# ATM90E26_Featherwing.net
KiCad netlist of a schematic drawn in EAGLE
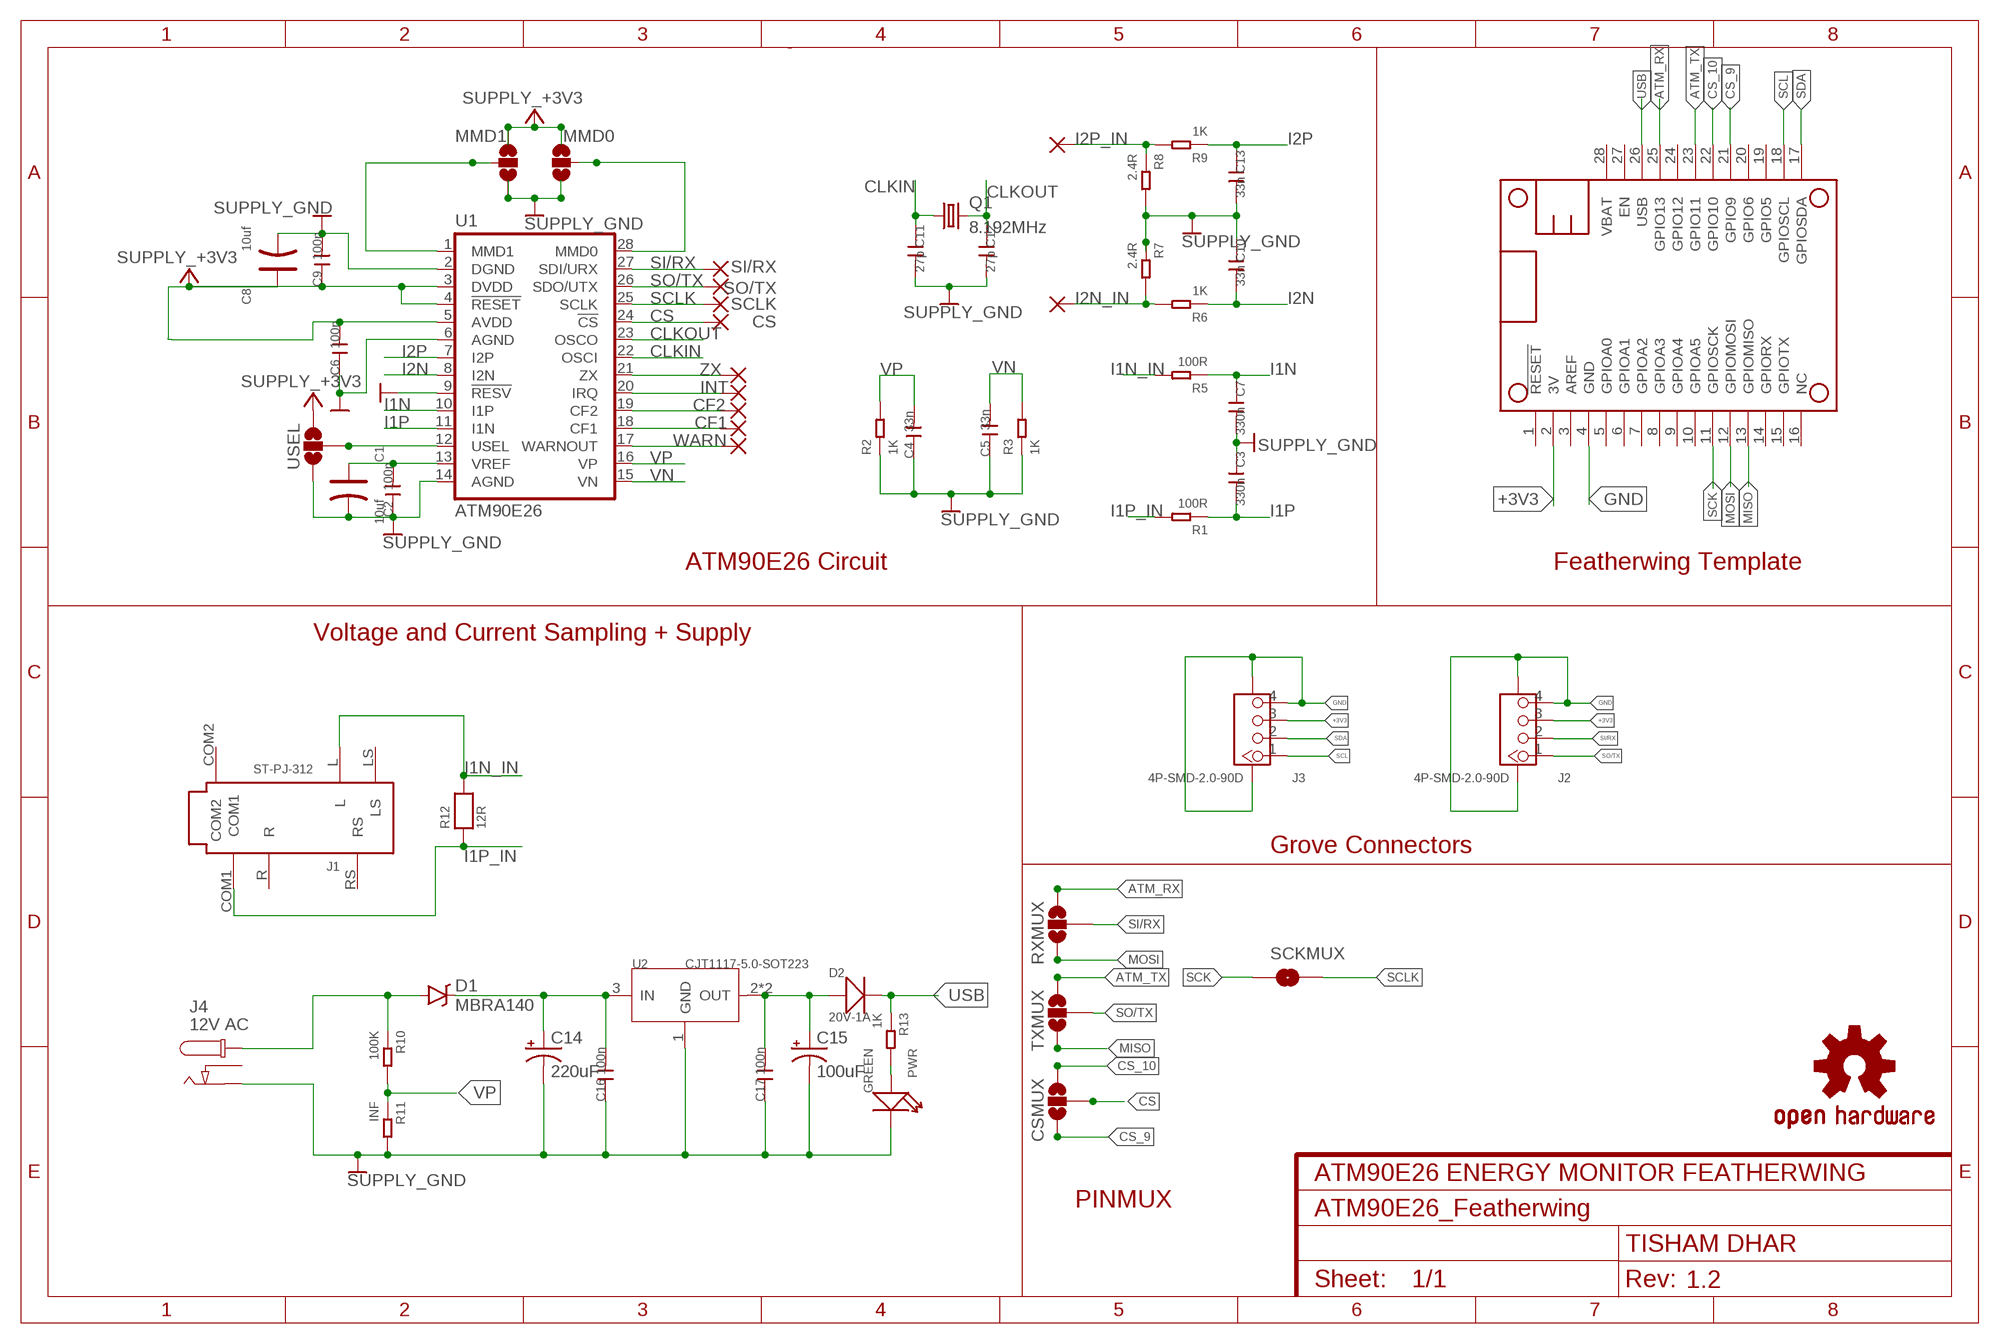
[diagram p0: schematic, sheet 1]

(export (version "E")
  (design (tool "Eeschema 10.0.6"))
  (components
    (comp (ref "C1")
      (value "10uf")
      (footprint "eagle-import:AVX-A")
      (fields (field (name "MPN") "TAJA226*010#NJ"))
      (libsource (lib "eagle-import") (part "TANTALUM-SMD-22UF-10V(AVX-A)"))
    )
    (comp (ref "C2")
      (value "100n")
      (footprint "eagle-import:C0603")
      (libsource (lib "eagle-import") (part "C-0603"))
    )
    (comp (ref "C3")
      (value "330n")
      (footprint "eagle-import:C0603")
      (libsource (lib "eagle-import") (part "C-0603"))
    )
    (comp (ref "C4")
      (value "33n")
      (footprint "eagle-import:C0603")
      (libsource (lib "eagle-import") (part "C-0603"))
    )
    (comp (ref "C5")
      (value "33n")
      (footprint "eagle-import:C0603")
      (libsource (lib "eagle-import") (part "C-0603"))
    )
    (comp (ref "C6")
      (value "100n")
      (footprint "eagle-import:C0603")
      (libsource (lib "eagle-import") (part "C-0603"))
    )
    (comp (ref "C7")
      (value "330n")
      (footprint "eagle-import:C0603")
      (libsource (lib "eagle-import") (part "C-0603"))
    )
    (comp (ref "C8")
      (value "10uf")
      (footprint "eagle-import:AVX-A")
      (fields (field (name "MPN") "TAJA226*010#NJ"))
      (libsource (lib "eagle-import") (part "TANTALUM-SMD-22UF-10V(AVX-A)"))
    )
    (comp (ref "C9")
      (value "100n")
      (footprint "eagle-import:C0603")
      (libsource (lib "eagle-import") (part "C-0603"))
    )
    (comp (ref "C10")
      (value "33n")
      (footprint "eagle-import:C0603")
      (libsource (lib "eagle-import") (part "C-0603"))
    )
    (comp (ref "C11")
      (value "27p")
      (footprint "eagle-import:C0603")
      (libsource (lib "eagle-import") (part "C-0603"))
    )
    (comp (ref "C12")
      (value "27p")
      (footprint "eagle-import:C0603")
      (libsource (lib "eagle-import") (part "C-0603"))
    )
    (comp (ref "C13")
      (value "33n")
      (footprint "eagle-import:C0603")
      (libsource (lib "eagle-import") (part "C-0603"))
    )
    (comp (ref "C14")
      (value "220uF")
      (footprint "eagle-import:140CLH-1010")
      (libsource (lib "eagle-import") (part "CPOL-US140CLH-1010"))
    )
    (comp (ref "C15")
      (value "100uF")
      (footprint "eagle-import:153CLV-0605")
      (libsource (lib "eagle-import") (part "CPOL-US153CLV-0605"))
    )
    (comp (ref "C16")
      (value "100n")
      (footprint "eagle-import:C0603")
      (libsource (lib "eagle-import") (part "C-0603"))
    )
    (comp (ref "C17")
      (value "100n")
      (footprint "eagle-import:C0603")
      (libsource (lib "eagle-import") (part "C-0603"))
    )
    (comp (ref "CF1")
      (value "WIREPADSMD1,27-254")
      (footprint "eagle-import:SMD1,27-2,54")
      (libsource (lib "eagle-import") (part "WIREPADSMD1,27-254"))
    )
    (comp (ref "CF2")
      (value "WIREPADSMD1,27-254")
      (footprint "eagle-import:SMD1,27-2,54")
      (libsource (lib "eagle-import") (part "WIREPADSMD1,27-254"))
    )
    (comp (ref "CS")
      (value "WIREPADSMD1,27-254")
      (footprint "eagle-import:SMD1,27-2,54")
      (libsource (lib "eagle-import") (part "WIREPADSMD1,27-254"))
    )
    (comp (ref "CSMUX")
      (value "JUMPER-PAD-3-NOYES_SILK")
      (footprint "eagle-import:PAD-JUMPER-3-NO_YES_SILK")
      (libsource (lib "eagle-import") (part "JUMPER-PAD-3-NOYES_SILK"))
    )
    (comp (ref "D1")
      (value "MBRA140")
      (footprint "eagle-import:SMA-DIODE")
      (libsource (lib "eagle-import") (part "MBRA140"))
    )
    (comp (ref "D2")
      (value "20V-1A")
      (footprint "eagle-import:SOD-123")
      (fields (field (name "MPN") "B5819W"))
      (libsource (lib "eagle-import") (part "SMD-DIODE-SCHOTTKY-20V-1A(SOD-123)"))
    )
    (comp (ref "I2N_IN")
      (value "WIREPADSMD1,27-254")
      (footprint "eagle-import:SMD1,27-2,54")
      (libsource (lib "eagle-import") (part "WIREPADSMD1,27-254"))
    )
    (comp (ref "I2P_IN")
      (value "WIREPADSMD1,27-254")
      (footprint "eagle-import:SMD1,27-2,54")
      (libsource (lib "eagle-import") (part "WIREPADSMD1,27-254"))
    )
    (comp (ref "INT")
      (value "WIREPADSMD1,27-254")
      (footprint "eagle-import:SMD1,27-2,54")
      (libsource (lib "eagle-import") (part "WIREPADSMD1,27-254"))
    )
    (comp (ref "J1")
      (value "ST-PJ-312")
      (footprint "eagle-import:AUDIO6P-SMD-3.5-14.0X6.4X5.0MM")
      (libsource (lib "eagle-import") (part "AUDIO-JACK-6P-SMD(ST-PJ-312)"))
    )
    (comp (ref "J2")
      (value "4P-SMD-2.0-90D")
      (footprint "eagle-import:HW4-SMD-2.0-90D")
      (libsource (lib "eagle-import") (part "GROVE-CONNECTOR-SMD-90D(4+2P-2.0)"))
    )
    (comp (ref "J3")
      (value "4P-SMD-2.0-90D")
      (footprint "eagle-import:HW4-SMD-2.0-90D")
      (libsource (lib "eagle-import") (part "GROVE-CONNECTOR-SMD-90D(4+2P-2.0)"))
    )
    (comp (ref "J4")
      (value "12V AC")
      (footprint "eagle-import:DC_BARREL_JACK_SMD_2MM")
      (libsource (lib "eagle-import") (part "CON_DC_M-DC_SMD"))
    )
    (comp (ref "LOGO1")
      (value "OSHW-LOGOM")
      (footprint "eagle-import:OSHW-LOGO-M")
      (libsource (lib "eagle-import") (part "OSHW-LOGOM"))
    )
    (comp (ref "MMD0")
      (value "JUMPER-PAD-3-NOFULL_BOX_SILK")
      (footprint "eagle-import:PAD-JUMPER-3-NO_YES_SILK_FULL_BOX")
      (libsource (lib "eagle-import") (part "JUMPER-PAD-3-NOFULL_BOX_SILK"))
    )
    (comp (ref "MMD1")
      (value "JUMPER-PAD-3-NOFULL_BOX_SILK")
      (footprint "eagle-import:PAD-JUMPER-3-NO_YES_SILK_FULL_BOX")
      (libsource (lib "eagle-import") (part "JUMPER-PAD-3-NOFULL_BOX_SILK"))
    )
    (comp (ref "MS1")
      (value "FEATHERWING_NODIM")
      (footprint "eagle-import:FEATHERWING_DIM")
      (libsource (lib "eagle-import") (part "FEATHERWING_NODIM"))
    )
    (comp (ref "PWR")
      (value "GREEN")
      (footprint "eagle-import:LED-0603")
      (libsource (lib "eagle-import") (part "LED'0603'"))
    )
    (comp (ref "Q1")
      (value "8.192MHz")
      (footprint "eagle-import:HC49UP")
      (libsource (lib "eagle-import") (part "CRYSTALHC49UP"))
    )
    (comp (ref "R1")
      (value "100R")
      (footprint "eagle-import:R0603")
      (fields (field (name "MPN") "RC0603FR-071KL"))
      (libsource (lib "eagle-import") (part "SMD-RES-1K(0603)"))
    )
    (comp (ref "R2")
      (value "1K")
      (footprint "eagle-import:R0603")
      (fields (field (name "MPN") "RC0603FR-071KL"))
      (libsource (lib "eagle-import") (part "SMD-RES-1K(0603)"))
    )
    (comp (ref "R3")
      (value "1K")
      (footprint "eagle-import:R0603")
      (fields (field (name "MPN") "RC0603FR-071KL"))
      (libsource (lib "eagle-import") (part "SMD-RES-1K(0603)"))
    )
    (comp (ref "R5")
      (value "100R")
      (footprint "eagle-import:R0603")
      (fields (field (name "MPN") "RC0603FR-071KL"))
      (libsource (lib "eagle-import") (part "SMD-RES-1K(0603)"))
    )
    (comp (ref "R6")
      (value "1K")
      (footprint "eagle-import:R0603")
      (fields (field (name "MPN") "RC0603FR-071KL"))
      (libsource (lib "eagle-import") (part "SMD-RES-1K(0603)"))
    )
    (comp (ref "R7")
      (value "2.4R")
      (footprint "eagle-import:R0603")
      (fields (field (name "MPN") "RC0603FR-071KL"))
      (libsource (lib "eagle-import") (part "SMD-RES-1K(0603)"))
    )
    (comp (ref "R8")
      (value "2.4R")
      (footprint "eagle-import:R0603")
      (fields (field (name "MPN") "RC0603FR-071KL"))
      (libsource (lib "eagle-import") (part "SMD-RES-1K(0603)"))
    )
    (comp (ref "R9")
      (value "1K")
      (footprint "eagle-import:R0603")
      (fields (field (name "MPN") "RC0603FR-071KL"))
      (libsource (lib "eagle-import") (part "SMD-RES-1K(0603)"))
    )
    (comp (ref "R10")
      (value "100K")
      (footprint "eagle-import:R0603")
      (fields (field (name "MPN") "RC0603JR-070RL"))
      (libsource (lib "eagle-import") (part "SMD-RES-0R(0603)"))
    )
    (comp (ref "R11")
      (value "INF")
      (footprint "eagle-import:R0603")
      (fields (field (name "MPN") "RC0603JR-070RL"))
      (libsource (lib "eagle-import") (part "SMD-RES-0R(0603)"))
    )
    (comp (ref "R12")
      (value "12R")
      (footprint "eagle-import:0805")
      (libsource (lib "eagle-import") (part "RESISTOR0805"))
    )
    (comp (ref "R13")
      (value "1K")
      (footprint "eagle-import:R0603")
      (fields (field (name "MPN") "RC0603JR-070RL"))
      (libsource (lib "eagle-import") (part "SMD-RES-0R(0603)"))
    )
    (comp (ref "RXMUX")
      (value "JUMPER-PAD-3-NOYES_SILK")
      (footprint "eagle-import:PAD-JUMPER-3-NO_YES_SILK")
      (libsource (lib "eagle-import") (part "JUMPER-PAD-3-NOYES_SILK"))
    )
    (comp (ref "SCKMUX")
      (value "JUMPER-PAD-2-NOYES_SILK")
      (footprint "eagle-import:PAD-JUMPER-2-NO_YES_SILK")
      (libsource (lib "eagle-import") (part "JUMPER-PAD-2-NOYES_SILK"))
    )
    (comp (ref "SCLK")
      (value "WIREPADSMD1,27-254")
      (footprint "eagle-import:SMD1,27-2,54")
      (libsource (lib "eagle-import") (part "WIREPADSMD1,27-254"))
    )
    (comp (ref "SI/RX")
      (value "WIREPADSMD1,27-254")
      (footprint "eagle-import:SMD1,27-2,54")
      (libsource (lib "eagle-import") (part "WIREPADSMD1,27-254"))
    )
    (comp (ref "SO/TX")
      (value "WIREPADSMD1,27-254")
      (footprint "eagle-import:SMD1,27-2,54")
      (libsource (lib "eagle-import") (part "WIREPADSMD1,27-254"))
    )
    (comp (ref "TXMUX")
      (value "JUMPER-PAD-3-NOYES_SILK")
      (footprint "eagle-import:PAD-JUMPER-3-NO_YES_SILK")
      (libsource (lib "eagle-import") (part "JUMPER-PAD-3-NOYES_SILK"))
    )
    (comp (ref "U1")
      (value "ATM90E26")
      (footprint "eagle-import:SSOP-28")
      (fields (field (name "MANF") "Atmel"))
      (libsource (lib "eagle-import") (part "ATM90E26"))
    )
    (comp (ref "U2")
      (value "CJT1117-5.0-SOT223")
      (footprint "eagle-import:SOT-223")
      (fields (field (name "MPN") "CJT1117-5.0"))
      (libsource (lib "eagle-import") (part "PMIC-CJT1117-5.0(SOT223)"))
    )
    (comp (ref "USEL")
      (value "JUMPER-PAD-3-NOFULL_BOX_SILK")
      (footprint "eagle-import:PAD-JUMPER-3-NO_YES_SILK_FULL_BOX")
      (libsource (lib "eagle-import") (part "JUMPER-PAD-3-NOFULL_BOX_SILK"))
    )
    (comp (ref "WARN")
      (value "WIREPADSMD1,27-254")
      (footprint "eagle-import:SMD1,27-2,54")
      (libsource (lib "eagle-import") (part "WIREPADSMD1,27-254"))
    )
    (comp (ref "ZX")
      (value "WIREPADSMD1,27-254")
      (footprint "eagle-import:SMD1,27-2,54")
      (libsource (lib "eagle-import") (part "WIREPADSMD1,27-254"))
    )
  )
  (nets
    (net (code "1") (name "+3V3") (class "Default")
      (node (ref "C6") (pin "2") (pinfunction "2_2") (pintype "passive"))
      (node (ref "C8") (pin "+") (pinfunction "+_+") (pintype "passive"))
      (node (ref "C9") (pin "1") (pinfunction "1_1") (pintype "passive"))
      (node (ref "J2") (pin "3") (pinfunction "3_3") (pintype "bidirectional"))
      (node (ref "J3") (pin "3") (pinfunction "3_3") (pintype "bidirectional"))
      (node (ref "MMD0") (pin "3") (pinfunction "3_3") (pintype "passive"))
      (node (ref "MMD1") (pin "1") (pinfunction "1_1") (pintype "passive"))
      (node (ref "MS1") (pin "2") (pinfunction "3V_2") (pintype "power_in"))
      (node (ref "U1") (pin "3") (pinfunction "DVDD_3") (pintype "power_in"))
      (node (ref "U1") (pin "4") (pinfunction "~{RESET}_4") (pintype "input"))
      (node (ref "U1") (pin "5") (pinfunction "AVDD_5") (pintype "power_in"))
      (node (ref "USEL") (pin "3") (pinfunction "3_3") (pintype "passive"))
    )
    (net (code "2") (name "/CLKIN") (class "Default")
      (node (ref "C11") (pin "1") (pinfunction "1_1") (pintype "passive"))
      (node (ref "Q1") (pin "1") (pinfunction "1_1") (pintype "passive"))
      (node (ref "U1") (pin "22") (pinfunction "OSCI_22") (pintype "input"))
    )
    (net (code "3") (name "/CLKOUT") (class "Default")
      (node (ref "C12") (pin "1") (pinfunction "1_1") (pintype "passive"))
      (node (ref "Q1") (pin "2") (pinfunction "2_2") (pintype "passive"))
      (node (ref "U1") (pin "23") (pinfunction "OSCO_23") (pintype "output"))
    )
    (net (code "4") (name "/I1N") (class "Default")
      (node (ref "C7") (pin "1") (pinfunction "1_1") (pintype "passive"))
      (node (ref "R5") (pin "1") (pinfunction "1_1") (pintype "passive"))
      (node (ref "U1") (pin "10") (pinfunction "I1P_10") (pintype "input"))
    )
    (net (code "5") (name "/I1N_IN") (class "Default")
      (node (ref "J1") (pin "L") (pinfunction "L_L") (pintype "bidirectional"))
      (node (ref "R12") (pin "2") (pinfunction "2_2") (pintype "passive"))
      (node (ref "R5") (pin "2") (pinfunction "2_2") (pintype "passive"))
    )
    (net (code "6") (name "/I1P") (class "Default")
      (node (ref "C3") (pin "2") (pinfunction "2_2") (pintype "passive"))
      (node (ref "R1") (pin "1") (pinfunction "1_1") (pintype "passive"))
      (node (ref "U1") (pin "11") (pinfunction "I1N_11") (pintype "input"))
    )
    (net (code "7") (name "/I1P_IN") (class "Default")
      (node (ref "J1") (pin "COM1") (pinfunction "COM1_COM1") (pintype "bidirectional"))
      (node (ref "R1") (pin "2") (pinfunction "2_2") (pintype "passive"))
      (node (ref "R12") (pin "1") (pinfunction "1_1") (pintype "passive"))
    )
    (net (code "8") (name "/I2N") (class "Default")
      (node (ref "C10") (pin "2") (pinfunction "2_2") (pintype "passive"))
      (node (ref "R6") (pin "1") (pinfunction "1_1") (pintype "passive"))
      (node (ref "U1") (pin "8") (pinfunction "I2N_8") (pintype "input"))
    )
    (net (code "9") (name "/I2N_IN") (class "Default")
      (node (ref "I2N_IN") (pin "1") (pinfunction "P_1") (pintype "passive"))
      (node (ref "R6") (pin "2") (pinfunction "2_2") (pintype "passive"))
      (node (ref "R7") (pin "2") (pinfunction "2_2") (pintype "passive"))
    )
    (net (code "10") (name "/I2P") (class "Default")
      (node (ref "C13") (pin "1") (pinfunction "1_1") (pintype "passive"))
      (node (ref "R9") (pin "1") (pinfunction "1_1") (pintype "passive"))
      (node (ref "U1") (pin "7") (pinfunction "I2P_7") (pintype "input"))
    )
    (net (code "11") (name "/I2P_IN") (class "Default")
      (node (ref "I2P_IN") (pin "1") (pinfunction "P_1") (pintype "passive"))
      (node (ref "R8") (pin "1") (pinfunction "1_1") (pintype "passive"))
      (node (ref "R9") (pin "2") (pinfunction "2_2") (pintype "passive"))
    )
    (net (code "12") (name "/VBAT") (class "Default")
      (node (ref "MS1") (pin "28") (pinfunction "VBAT_28") (pintype "power_in"))
    )
    (net (code "13") (name "/VN") (class "Default")
      (node (ref "C5") (pin "2") (pinfunction "2_2") (pintype "passive"))
      (node (ref "R3") (pin "2") (pinfunction "2_2") (pintype "passive"))
      (node (ref "U1") (pin "15") (pinfunction "VN_15") (pintype "input"))
    )
    (net (code "14") (name "ATM_RX") (class "Default")
      (node (ref "MS1") (pin "25") (pinfunction "GPIO13_25") (pintype "bidirectional"))
      (node (ref "RXMUX") (pin "3") (pinfunction "3_3") (pintype "passive"))
    )
    (net (code "15") (name "ATM_TX") (class "Default")
      (node (ref "MS1") (pin "23") (pinfunction "GPIO11_23") (pintype "bidirectional"))
      (node (ref "TXMUX") (pin "3") (pinfunction "3_3") (pintype "passive"))
    )
    (net (code "16") (name "CS") (class "Default")
      (node (ref "CS") (pin "1") (pinfunction "P_1") (pintype "passive"))
      (node (ref "CSMUX") (pin "2") (pinfunction "2_2") (pintype "passive"))
      (node (ref "U1") (pin "24") (pinfunction "~{CS}_24") (pintype "input"))
    )
    (net (code "17") (name "CS_9") (class "Default")
      (node (ref "CSMUX") (pin "1") (pinfunction "1_1") (pintype "passive"))
      (node (ref "MS1") (pin "21") (pinfunction "GPIO9_21") (pintype "bidirectional"))
    )
    (net (code "18") (name "CS_10") (class "Default")
      (node (ref "CSMUX") (pin "3") (pinfunction "3_3") (pintype "passive"))
      (node (ref "MS1") (pin "22") (pinfunction "GPIO10_22") (pintype "bidirectional"))
    )
    (net (code "19") (name "GND") (class "Default")
      (node (ref "C1") (pin "-") (pinfunction "-_-") (pintype "passive"))
      (node (ref "C10") (pin "1") (pinfunction "1_1") (pintype "passive"))
      (node (ref "C11") (pin "2") (pinfunction "2_2") (pintype "passive"))
      (node (ref "C12") (pin "2") (pinfunction "2_2") (pintype "passive"))
      (node (ref "C13") (pin "2") (pinfunction "2_2") (pintype "passive"))
      (node (ref "C14") (pin "-") (pinfunction "-_-") (pintype "passive"))
      (node (ref "C15") (pin "-") (pinfunction "-_-") (pintype "passive"))
      (node (ref "C16") (pin "1") (pinfunction "1_1") (pintype "passive"))
      (node (ref "C17") (pin "1") (pinfunction "1_1") (pintype "passive"))
      (node (ref "C2") (pin "1") (pinfunction "1_1") (pintype "passive"))
      (node (ref "C3") (pin "1") (pinfunction "1_1") (pintype "passive"))
      (node (ref "C4") (pin "1") (pinfunction "1_1") (pintype "passive"))
      (node (ref "C5") (pin "1") (pinfunction "1_1") (pintype "passive"))
      (node (ref "C6") (pin "1") (pinfunction "1_1") (pintype "passive"))
      (node (ref "C7") (pin "2") (pinfunction "2_2") (pintype "passive"))
      (node (ref "C8") (pin "-") (pinfunction "-_-") (pintype "passive"))
      (node (ref "C9") (pin "2") (pinfunction "2_2") (pintype "passive"))
      (node (ref "J2") (pin "4") (pinfunction "4_4") (pintype "bidirectional"))
      (node (ref "J2") (pin "SS1") (pinfunction "SS1_SS1") (pintype "bidirectional"))
      (node (ref "J2") (pin "SS2") (pinfunction "SS2_SS2") (pintype "bidirectional"))
      (node (ref "J3") (pin "4") (pinfunction "4_4") (pintype "bidirectional"))
      (node (ref "J3") (pin "SS1") (pinfunction "SS1_SS1") (pintype "bidirectional"))
      (node (ref "J3") (pin "SS2") (pinfunction "SS2_SS2") (pintype "bidirectional"))
      (node (ref "J4") (pin "P2") (pinfunction "P2_P2") (pintype "passive"))
      (node (ref "MMD0") (pin "1") (pinfunction "1_1") (pintype "passive"))
      (node (ref "MMD1") (pin "3") (pinfunction "3_3") (pintype "passive"))
      (node (ref "MS1") (pin "4") (pinfunction "GND_4") (pintype "power_in"))
      (node (ref "PWR") (pin "-") (pinfunction "-_-") (pintype "passive"))
      (node (ref "R11") (pin "2") (pinfunction "2_2") (pintype "passive"))
      (node (ref "R2") (pin "1") (pinfunction "1_1") (pintype "passive"))
      (node (ref "R3") (pin "1") (pinfunction "1_1") (pintype "passive"))
      (node (ref "R7") (pin "1") (pinfunction "1_1") (pintype "passive"))
      (node (ref "R8") (pin "2") (pinfunction "2_2") (pintype "passive"))
      (node (ref "U1") (pin "14") (pinfunction "AGND_14") (pintype "power_in"))
      (node (ref "U1") (pin "2") (pinfunction "DGND_2") (pintype "power_in"))
      (node (ref "U1") (pin "6") (pinfunction "AGND_6") (pintype "power_in"))
      (node (ref "U1") (pin "9") (pinfunction "~{RESV}_9") (pintype "input"))
      (node (ref "U2") (pin "1") (pinfunction "GND_1") (pintype "bidirectional"))
      (node (ref "USEL") (pin "1") (pinfunction "1_1") (pintype "passive"))
    )
    (net (code "20") (name "MISO") (class "Default")
      (node (ref "MS1") (pin "13") (pinfunction "GPIOMISO_13") (pintype "bidirectional"))
      (node (ref "TXMUX") (pin "1") (pinfunction "1_1") (pintype "passive"))
    )
    (net (code "21") (name "MOSI") (class "Default")
      (node (ref "MS1") (pin "12") (pinfunction "GPIOMOSI_12") (pintype "bidirectional"))
      (node (ref "RXMUX") (pin "1") (pinfunction "1_1") (pintype "passive"))
    )
    (net (code "22") (name "Net-(C15-Pad+)") (class "Default")
      (node (ref "C15") (pin "+") (pinfunction "+_+") (pintype "passive"))
      (node (ref "C17") (pin "2") (pinfunction "2_2") (pintype "passive"))
      (node (ref "D2") (pin "+") (pinfunction "+_+") (pintype "passive"))
      (node (ref "U2") (pin "2") (pinfunction "OUT_2") (pintype "bidirectional"))
      (node (ref "U2") (pin "TER") (pinfunction "OUT_TER") (pintype "bidirectional"))
    )
    (net (code "23") (name "Net-(CF1-P)") (class "Default")
      (node (ref "CF1") (pin "1") (pinfunction "P_1") (pintype "passive"))
      (node (ref "U1") (pin "18") (pinfunction "CF1_18") (pintype "output"))
    )
    (net (code "24") (name "Net-(CF2-P)") (class "Default")
      (node (ref "CF2") (pin "1") (pinfunction "P_1") (pintype "passive"))
      (node (ref "U1") (pin "19") (pinfunction "CF2_19") (pintype "output"))
    )
    (net (code "25") (name "Net-(INT-P)") (class "Default")
      (node (ref "INT") (pin "1") (pinfunction "P_1") (pintype "passive"))
      (node (ref "U1") (pin "20") (pinfunction "IRQ_20") (pintype "output"))
    )
    (net (code "26") (name "Net-(J4-P1)") (class "Default")
      (node (ref "D1") (pin "A") (pinfunction "A_A") (pintype "passive"))
      (node (ref "J4") (pin "P1@2") (pinfunction "P1_P1@2") (pintype "passive"))
      (node (ref "R10") (pin "1") (pinfunction "1_1") (pintype "passive"))
    )
    (net (code "27") (name "Net-(PWR-Pad+)") (class "Default")
      (node (ref "PWR") (pin "+") (pinfunction "+_+") (pintype "passive"))
      (node (ref "R13") (pin "2") (pinfunction "2_2") (pintype "passive"))
    )
    (net (code "28") (name "Net-(U1-MMD0)") (class "Default")
      (node (ref "MMD0") (pin "2") (pinfunction "2_2") (pintype "passive"))
      (node (ref "U1") (pin "28") (pinfunction "MMD0_28") (pintype "input"))
    )
    (net (code "29") (name "Net-(U1-MMD1)") (class "Default")
      (node (ref "MMD1") (pin "2") (pinfunction "2_2") (pintype "passive"))
      (node (ref "U1") (pin "1") (pinfunction "MMD1_1") (pintype "input"))
    )
    (net (code "30") (name "Net-(U1-USEL)") (class "Default")
      (node (ref "U1") (pin "12") (pinfunction "USEL_12") (pintype "input"))
      (node (ref "USEL") (pin "2") (pinfunction "2_2") (pintype "passive"))
    )
    (net (code "31") (name "Net-(U1-VREF)") (class "Default")
      (node (ref "C1") (pin "+") (pinfunction "+_+") (pintype "passive"))
      (node (ref "C2") (pin "2") (pinfunction "2_2") (pintype "passive"))
      (node (ref "U1") (pin "13") (pinfunction "VREF_13") (pintype "power_in"))
    )
    (net (code "32") (name "Net-(U1-WARNOUT)") (class "Default")
      (node (ref "U1") (pin "17") (pinfunction "WARNOUT_17") (pintype "output"))
      (node (ref "WARN") (pin "1") (pinfunction "P_1") (pintype "passive"))
    )
    (net (code "33") (name "Net-(U1-ZX)") (class "Default")
      (node (ref "U1") (pin "21") (pinfunction "ZX_21") (pintype "bidirectional"))
      (node (ref "ZX") (pin "1") (pinfunction "P_1") (pintype "passive"))
    )
    (net (code "34") (name "Net-(U2-IN)") (class "Default")
      (node (ref "C14") (pin "+") (pinfunction "+_+") (pintype "passive"))
      (node (ref "C16") (pin "2") (pinfunction "2_2") (pintype "passive"))
      (node (ref "D1") (pin "C") (pinfunction "C_C") (pintype "passive"))
      (node (ref "U2") (pin "3") (pinfunction "IN_3") (pintype "bidirectional"))
    )
    (net (code "35") (name "SCK") (class "Default")
      (node (ref "MS1") (pin "11") (pinfunction "GPIOSCK_11") (pintype "bidirectional"))
      (node (ref "SCKMUX") (pin "1") (pinfunction "1_1") (pintype "passive"))
    )
    (net (code "36") (name "SCL") (class "Default")
      (node (ref "J3") (pin "1") (pinfunction "1_1") (pintype "bidirectional"))
      (node (ref "MS1") (pin "18") (pinfunction "GPIOSCL_18") (pintype "bidirectional"))
    )
    (net (code "37") (name "SCLK") (class "Default")
      (node (ref "SCKMUX") (pin "2") (pinfunction "2_2") (pintype "passive"))
      (node (ref "SCLK") (pin "1") (pinfunction "P_1") (pintype "passive"))
      (node (ref "U1") (pin "25") (pinfunction "SCLK_25") (pintype "input"))
    )
    (net (code "38") (name "SDA") (class "Default")
      (node (ref "J3") (pin "2") (pinfunction "2_2") (pintype "bidirectional"))
      (node (ref "MS1") (pin "17") (pinfunction "GPIOSDA_17") (pintype "bidirectional"))
    )
    (net (code "39") (name "SI{slash}RX") (class "Default")
      (node (ref "J2") (pin "2") (pinfunction "2_2") (pintype "bidirectional"))
      (node (ref "RXMUX") (pin "2") (pinfunction "2_2") (pintype "passive"))
      (node (ref "SI/RX") (pin "1") (pinfunction "P_1") (pintype "passive"))
      (node (ref "U1") (pin "27") (pinfunction "SDI/URX_27") (pintype "input"))
    )
    (net (code "40") (name "SO{slash}TX") (class "Default")
      (node (ref "J2") (pin "1") (pinfunction "1_1") (pintype "bidirectional"))
      (node (ref "SO/TX") (pin "1") (pinfunction "P_1") (pintype "passive"))
      (node (ref "TXMUX") (pin "2") (pinfunction "2_2") (pintype "passive"))
      (node (ref "U1") (pin "26") (pinfunction "SDO/UTX_26") (pintype "output"))
    )
    (net (code "41") (name "USB") (class "Default")
      (node (ref "D2") (pin "-") (pinfunction "-_-") (pintype "passive"))
      (node (ref "MS1") (pin "26") (pinfunction "USB_26") (pintype "power_in"))
      (node (ref "R13") (pin "1") (pinfunction "1_1") (pintype "passive"))
    )
    (net (code "42") (name "VP") (class "Default")
      (node (ref "C4") (pin "2") (pinfunction "2_2") (pintype "passive"))
      (node (ref "R10") (pin "2") (pinfunction "2_2") (pintype "passive"))
      (node (ref "R11") (pin "1") (pinfunction "1_1") (pintype "passive"))
      (node (ref "R2") (pin "2") (pinfunction "2_2") (pintype "passive"))
      (node (ref "U1") (pin "16") (pinfunction "VP_16") (pintype "input"))
    )
    (net (code "43") (name "unconnected-(J1-PadCOM2)") (class "Default")
      (node (ref "J1") (pin "COM2") (pinfunction "COM2_COM2") (pintype "bidirectional"))
    )
    (net (code "44") (name "unconnected-(J1-PadLS)") (class "Default")
      (node (ref "J1") (pin "LS") (pinfunction "LS_LS") (pintype "bidirectional"))
    )
    (net (code "45") (name "unconnected-(J1-PadR)") (class "Default")
      (node (ref "J1") (pin "R") (pinfunction "R_R") (pintype "bidirectional"))
    )
    (net (code "46") (name "unconnected-(J1-PadRS)") (class "Default")
      (node (ref "J1") (pin "RS") (pinfunction "RS_RS") (pintype "bidirectional"))
    )
    (net (code "47") (name "unconnected-(J4-PadP3)") (class "Default")
      (node (ref "J4") (pin "P3") (pinfunction "P3_P3") (pintype "passive"))
    )
    (net (code "48") (name "unconnected-(MS1-AREF-Pad3)") (class "Default")
      (node (ref "MS1") (pin "3") (pinfunction "AREF_3") (pintype "passive"))
    )
    (net (code "49") (name "unconnected-(MS1-EN-Pad27)") (class "Default")
      (node (ref "MS1") (pin "27") (pinfunction "EN_27") (pintype "passive"))
    )
    (net (code "50") (name "unconnected-(MS1-GPIO5-Pad19)") (class "Default")
      (node (ref "MS1") (pin "19") (pinfunction "GPIO5_19") (pintype "bidirectional"))
    )
    (net (code "51") (name "unconnected-(MS1-GPIO6-Pad20)") (class "Default")
      (node (ref "MS1") (pin "20") (pinfunction "GPIO6_20") (pintype "bidirectional"))
    )
    (net (code "52") (name "unconnected-(MS1-GPIO12-Pad24)") (class "Default")
      (node (ref "MS1") (pin "24") (pinfunction "GPIO12_24") (pintype "bidirectional"))
    )
    (net (code "53") (name "unconnected-(MS1-GPIOA0-Pad5)") (class "Default")
      (node (ref "MS1") (pin "5") (pinfunction "GPIOA0_5") (pintype "bidirectional"))
    )
    (net (code "54") (name "unconnected-(MS1-GPIOA1-Pad6)") (class "Default")
      (node (ref "MS1") (pin "6") (pinfunction "GPIOA1_6") (pintype "bidirectional"))
    )
    (net (code "55") (name "unconnected-(MS1-GPIOA2-Pad7)") (class "Default")
      (node (ref "MS1") (pin "7") (pinfunction "GPIOA2_7") (pintype "bidirectional"))
    )
    (net (code "56") (name "unconnected-(MS1-GPIOA3-Pad8)") (class "Default")
      (node (ref "MS1") (pin "8") (pinfunction "GPIOA3_8") (pintype "bidirectional"))
    )
    (net (code "57") (name "unconnected-(MS1-GPIOA4-Pad9)") (class "Default")
      (node (ref "MS1") (pin "9") (pinfunction "GPIOA4_9") (pintype "bidirectional"))
    )
    (net (code "58") (name "unconnected-(MS1-GPIOA5-Pad10)") (class "Default")
      (node (ref "MS1") (pin "10") (pinfunction "GPIOA5_10") (pintype "bidirectional"))
    )
    (net (code "59") (name "unconnected-(MS1-GPIORX-Pad14)") (class "Default")
      (node (ref "MS1") (pin "14") (pinfunction "GPIORX_14") (pintype "bidirectional"))
    )
    (net (code "60") (name "unconnected-(MS1-GPIOTX-Pad15)") (class "Default")
      (node (ref "MS1") (pin "15") (pinfunction "GPIOTX_15") (pintype "bidirectional"))
    )
    (net (code "61") (name "unconnected-(MS1-NC-Pad16)") (class "Default")
      (node (ref "MS1") (pin "16") (pinfunction "NC_16") (pintype "passive"))
    )
    (net (code "62") (name "unconnected-(MS1-~{RESET}-Pad1)") (class "Default")
      (node (ref "MS1") (pin "1") (pinfunction "~{RESET}_1") (pintype "input"))
    )
  )
)
